# SDCard.net
KiCad netlist of a schematic drawn in Altium Designer
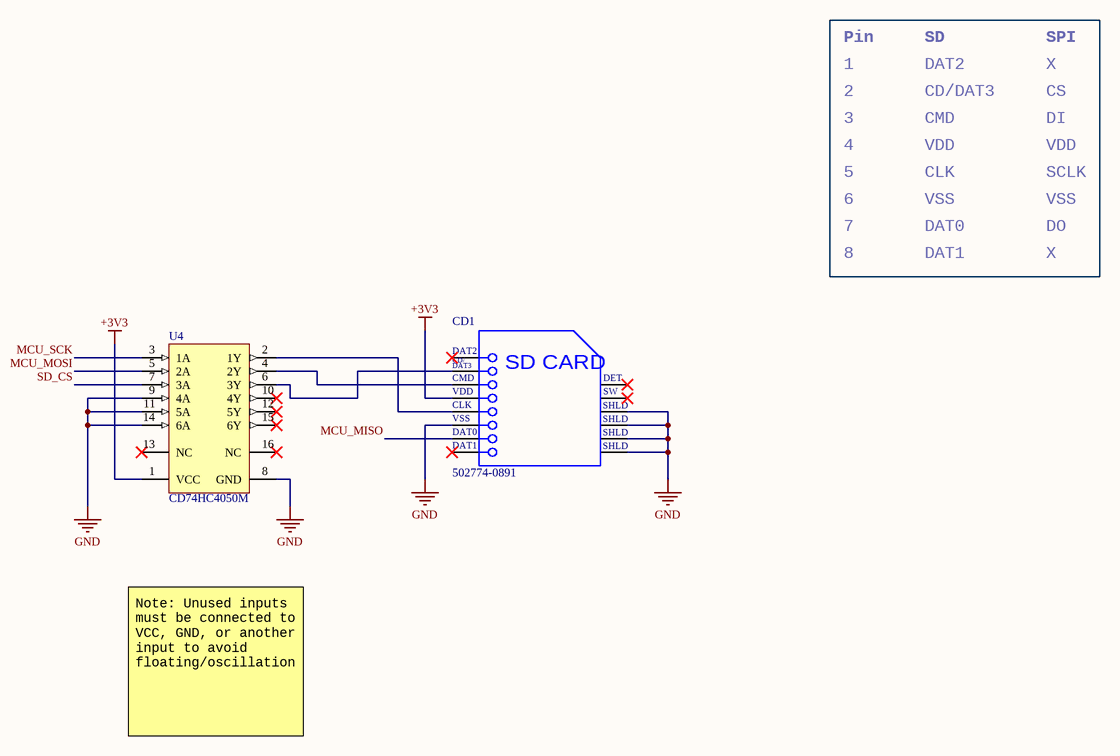
[diagram p0: SDCard.SchDoc]

(export (version "E")
  (design (tool "Eeschema 10.0.6"))
  (components
    (comp (ref "CD1")
      (value "502774-0891")
      (footprint "MOLX-502774-0891_V")
      (description "Micro SD Memory Card Connector, 0.5 A, 10 V (DC), -25 to 85 degC, 8-Pin SMT, RoHS, Tape and Reel")
      (fields (field (name "MANUFACTURER") "Molex"))
      (libsource (lib "Altium Content Vault") (part "CN-SD-8-2SW-4S_B"))
    )
    (comp (ref "U4")
      (value "CD74HC4050M")
      (footprint "D0016A_N")
      (description "High Speed CMOS Logic Hex Non-Inverting Buffers, D0016A, TUBE")
      (fields
        (field (name "MANUFACTURER") "Texas Instruments")
        (field (name "GENERIC PART NUMBER") "CD74HC4050")
      )
      (libsource (lib "Altium Content Vault") (part "TI-CDX4HC4050-16"))
    )
  )
  (nets
    (net (code "1") (name "+3V3") (class "Default")
      (node (ref "CD1") (pin "4") (pinfunction "VDD_4") (pintype "passive"))
      (node (ref "U4") (pin "1") (pinfunction "VCC_1") (pintype "power_in"))
    )
    (net (code "2") (name "/MCU_MISO") (class "Default")
      (node (ref "CD1") (pin "7") (pinfunction "DAT0_7") (pintype "passive"))
    )
    (net (code "3") (name "/MCU_MOSI") (class "Default")
      (node (ref "U4") (pin "5") (pinfunction "2A_5") (pintype "input"))
    )
    (net (code "4") (name "/MCU_SCK") (class "Default")
      (node (ref "U4") (pin "3") (pinfunction "1A_3") (pintype "input"))
    )
    (net (code "5") (name "/SD_CS") (class "Default")
      (node (ref "U4") (pin "7") (pinfunction "3A_7") (pintype "input"))
    )
    (net (code "6") (name "GND") (class "Default")
      (node (ref "CD1") (pin "11") (pinfunction "SHLD_11") (pintype "passive"))
      (node (ref "CD1") (pin "12") (pinfunction "SHLD_12") (pintype "passive"))
      (node (ref "CD1") (pin "13") (pinfunction "SHLD_13") (pintype "passive"))
      (node (ref "CD1") (pin "14") (pinfunction "SHLD_14") (pintype "passive"))
      (node (ref "CD1") (pin "6") (pinfunction "VSS_6") (pintype "passive"))
      (node (ref "U4") (pin "11") (pinfunction "5A_11") (pintype "input"))
      (node (ref "U4") (pin "14") (pinfunction "6A_14") (pintype "input"))
      (node (ref "U4") (pin "8") (pinfunction "GND_8") (pintype "power_in"))
      (node (ref "U4") (pin "9") (pinfunction "4A_9") (pintype "input"))
    )
    (net (code "7") (name "Net-(CD1-CD{slash}DAT3)") (class "Default")
      (node (ref "CD1") (pin "2") (pinfunction "CD/DAT3_2") (pintype "passive"))
      (node (ref "U4") (pin "6") (pinfunction "3Y_6") (pintype "output"))
    )
    (net (code "8") (name "Net-(CD1-CLK)") (class "Default")
      (node (ref "CD1") (pin "5") (pinfunction "CLK_5") (pintype "passive"))
      (node (ref "U4") (pin "2") (pinfunction "1Y_2") (pintype "output"))
    )
    (net (code "9") (name "Net-(CD1-CMD)") (class "Default")
      (node (ref "CD1") (pin "3") (pinfunction "CMD_3") (pintype "passive"))
      (node (ref "U4") (pin "4") (pinfunction "2Y_4") (pintype "output"))
    )
    (net (code "10") (name "unconnected-(CD1-DAT1-Pad8)") (class "Default")
      (node (ref "CD1") (pin "8") (pinfunction "DAT1_8") (pintype "passive+no_connect"))
    )
    (net (code "11") (name "unconnected-(CD1-DAT2-Pad1)") (class "Default")
      (node (ref "CD1") (pin "1") (pinfunction "DAT2_1") (pintype "passive+no_connect"))
    )
    (net (code "12") (name "unconnected-(CD1-DETECT-Pad9)") (class "Default")
      (node (ref "CD1") (pin "9") (pinfunction "DETECT_9") (pintype "passive+no_connect"))
    )
    (net (code "13") (name "unconnected-(CD1-SWITCH-Pad10)") (class "Default")
      (node (ref "CD1") (pin "10") (pinfunction "SWITCH_10") (pintype "passive+no_connect"))
    )
    (net (code "14") (name "unconnected-(U4-4Y-Pad10)") (class "Default")
      (node (ref "U4") (pin "10") (pinfunction "4Y_10") (pintype "output+no_connect"))
    )
    (net (code "15") (name "unconnected-(U4-5Y-Pad12)") (class "Default")
      (node (ref "U4") (pin "12") (pinfunction "5Y_12") (pintype "output+no_connect"))
    )
    (net (code "16") (name "unconnected-(U4-6Y-Pad15)") (class "Default")
      (node (ref "U4") (pin "15") (pinfunction "6Y_15") (pintype "output+no_connect"))
    )
    (net (code "17") (name "unconnected-(U4-NC-Pad13)") (class "Default")
      (node (ref "U4") (pin "13") (pinfunction "NC_13") (pintype "passive+no_connect"))
    )
    (net (code "18") (name "unconnected-(U4-NC-Pad16)") (class "Default")
      (node (ref "U4") (pin "16") (pinfunction "NC_16") (pintype "passive+no_connect"))
    )
  )
)
